# Sheet.net
KiCad netlist of a schematic drawn in Altium Designer
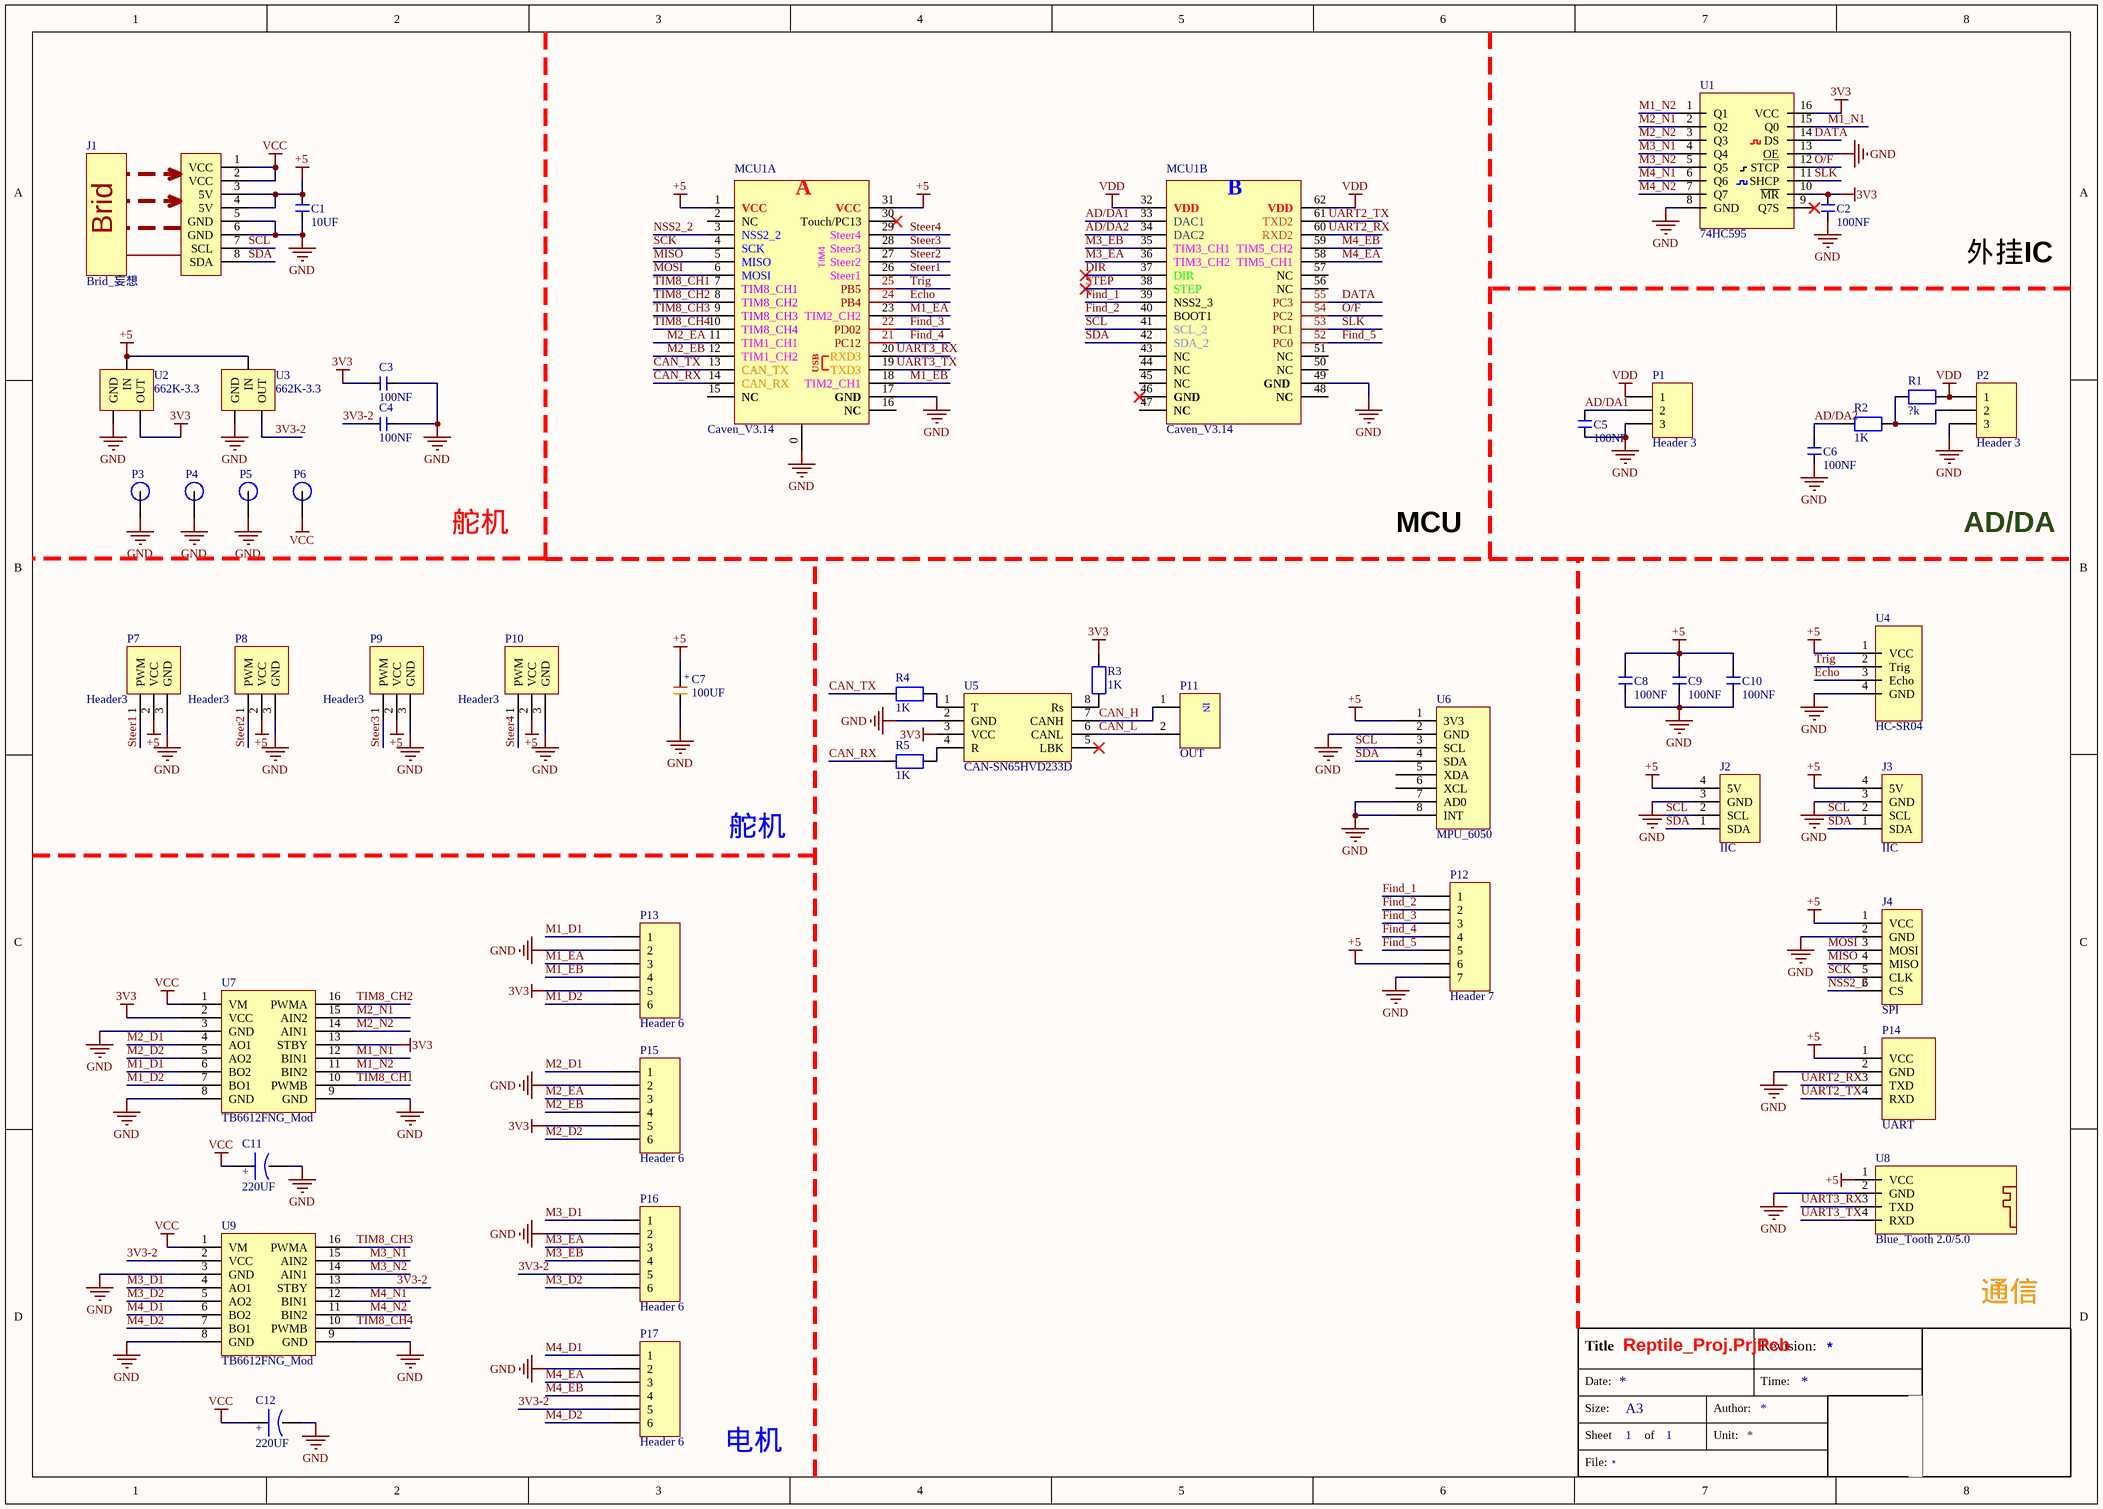
[diagram p0: Sheet.SchDoc]

(export (version "E")
  (design (tool "Eeschema 10.0.6"))
  (components
    (comp (ref "C1")
      (value "10UF")
      (footprint "CAP_1206")
      (description "CAP  12~50V")
      (libsource (lib "User") (part "CAP"))
    )
    (comp (ref "C2")
      (value "100NF")
      (footprint "CAP_0603")
      (description "CAP  12~50V")
      (libsource (lib "User") (part "CAP"))
    )
    (comp (ref "C3")
      (value "100NF")
      (footprint "CAP_0603")
      (description "CAP  12~50V")
      (libsource (lib "User") (part "CAP"))
    )
    (comp (ref "C4")
      (value "100NF")
      (footprint "CAP_0603")
      (description "CAP  12~50V")
      (libsource (lib "User") (part "CAP"))
    )
    (comp (ref "C5")
      (value "100NF")
      (footprint "CAP_0603")
      (description "CAP  12~50V")
      (libsource (lib "User") (part "CAP"))
    )
    (comp (ref "C6")
      (value "100NF")
      (footprint "CAP_0603")
      (description "CAP  12~50V")
      (libsource (lib "User") (part "CAP"))
    )
    (comp (ref "C7")
      (value "100UF")
      (footprint "CAP_3528_B")
      (description "CAP  6~12V  钽电容")
      (libsource (lib "User") (part "CAP_TA"))
    )
    (comp (ref "C8")
      (value "100NF")
      (footprint "CAP_0603")
      (description "CAP  12~50V")
      (libsource (lib "User") (part "CAP"))
    )
    (comp (ref "C9")
      (value "100NF")
      (footprint "CAP_0603")
      (description "CAP  12~50V")
      (libsource (lib "User") (part "CAP"))
    )
    (comp (ref "C10")
      (value "100NF")
      (footprint "CAP_0603")
      (description "CAP  12~50V")
      (libsource (lib "User") (part "CAP"))
    )
    (comp (ref "C11")
      (value "220UF")
      (footprint "CAPE_E")
      (description "CAP 12V ~ 50V   电解电容")
      (libsource (lib "User") (part "CAP_BIG"))
    )
    (comp (ref "C12")
      (value "220UF")
      (footprint "CAPE_E")
      (description "CAP 12V ~ 50V   电解电容")
      (libsource (lib "User") (part "CAP_BIG"))
    )
    (comp (ref "J1")
      (value "Brid_妄想")
      (footprint "Brid")
      (description "Brid")
      (libsource (lib "User") (part "Brid"))
    )
    (comp (ref "J2")
      (value "IIC")
      (footprint "Header 2.54X4")
      (description "Heard")
      (libsource (lib "User") (part "IIC"))
    )
    (comp (ref "J3")
      (value "IIC")
      (footprint "IIC-XH2.54-4PIN")
      (description "Heard")
      (libsource (lib "User") (part "IIC"))
    )
    (comp (ref "J4")
      (value "SPI")
      (footprint "Header 2.54X6")
      (description "Heard")
      (libsource (lib "User") (part "SPI"))
    )
    (comp (ref "MCU1")
      (value "Caven_V3.14")
      (footprint "Caven_3.14")
      (description "MCU_STM32F103RE")
      (libsource (lib "User") (part "Caven_V3.14"))
    )
    (comp (ref "P1")
      (value "Header 3")
      (footprint "Header 2.54X3")
      (description "Header, 3-Pin")
      (fields (field (name "PUBLISHER") "Altium Limited"))
      (libsource (lib "Miscellaneous Connectors") (part "Header 3"))
    )
    (comp (ref "P2")
      (value "Header 3")
      (footprint "Header 2.54X3")
      (description "Header, 3-Pin")
      (fields (field (name "PUBLISHER") "Altium Limited"))
      (libsource (lib "Miscellaneous Connectors") (part "Header 3"))
    )
    (comp (ref "P3")
      (value "铜柱6m")
      (footprint "M3x6_L-Type")
      (description "IN-OUT")
      (libsource (lib "User") (part "Pillar"))
    )
    (comp (ref "P4")
      (value "铜柱6m")
      (footprint "M3x6_L-Type")
      (description "IN-OUT")
      (libsource (lib "User") (part "Pillar"))
    )
    (comp (ref "P5")
      (value "铜柱6m")
      (footprint "M3x6_L-Type")
      (description "IN-OUT")
      (libsource (lib "User") (part "Pillar"))
    )
    (comp (ref "P6")
      (value "铜柱6m")
      (footprint "M3x6_L-Type")
      (description "IN-OUT")
      (libsource (lib "User") (part "Pillar"))
    )
    (comp (ref "P7")
      (value "Header3")
      (footprint "PWM_Steer-F")
      (description "Header")
      (libsource (lib "User") (part "PWM_D"))
    )
    (comp (ref "P8")
      (value "Header3")
      (footprint "PWM_Steer-B")
      (description "Header")
      (libsource (lib "User") (part "PWM_D"))
    )
    (comp (ref "P9")
      (value "Header3")
      (footprint "PWM_Steer-F")
      (description "Header")
      (libsource (lib "User") (part "PWM_D"))
    )
    (comp (ref "P10")
      (value "Header3")
      (footprint "PWM_Steer-B")
      (description "Header")
      (libsource (lib "User") (part "PWM_D"))
    )
    (comp (ref "P11")
      (value "OUT")
      (footprint "PIN-2_5.08")
      (description "Header")
      (libsource (lib "User") (part "IN _2PIN"))
    )
    (comp (ref "P12")
      (value "Header 7")
      (footprint "Header H 2.54X7")
      (description "Header, 7-Pin")
      (fields (field (name "PUBLISHER") "Altium Limited"))
      (libsource (lib "Miscellaneous Connectors") (part "Header 7"))
    )
    (comp (ref "P13")
      (value "Header 6")
      (footprint "XH2.54-WI-6P")
      (description "Header, 6-Pin")
      (fields (field (name "PUBLISHER") "Altium Limited"))
      (libsource (lib "Miscellaneous Connectors") (part "Header 6"))
    )
    (comp (ref "P14")
      (value "UART")
      (footprint "UART")
      (description "Header")
      (libsource (lib "User") (part "UART"))
    )
    (comp (ref "P15")
      (value "Header 6")
      (footprint "XH2.54-WI-6P")
      (description "Header, 6-Pin")
      (fields (field (name "PUBLISHER") "Altium Limited"))
      (libsource (lib "Miscellaneous Connectors") (part "Header 6"))
    )
    (comp (ref "P16")
      (value "Header 6")
      (footprint "XH2.54-WI-6P")
      (description "Header, 6-Pin")
      (fields (field (name "PUBLISHER") "Altium Limited"))
      (libsource (lib "Miscellaneous Connectors") (part "Header 6"))
    )
    (comp (ref "P17")
      (value "Header 6")
      (footprint "XH2.54-WI-6P")
      (description "Header, 6-Pin")
      (fields (field (name "PUBLISHER") "Altium Limited"))
      (libsource (lib "Miscellaneous Connectors") (part "Header 6"))
    )
    (comp (ref "R1")
      (value "?k")
      (footprint "RESC_0603_2")
      (description "RES 贴片")
      (libsource (lib "User") (part "RES"))
    )
    (comp (ref "R2")
      (value "1K")
      (footprint "RESC_0603_2")
      (description "RES 贴片")
      (libsource (lib "User") (part "RES"))
    )
    (comp (ref "R3")
      (value "1K")
      (footprint "RESC_0603_2")
      (description "RES 贴片")
      (libsource (lib "User") (part "RES"))
    )
    (comp (ref "R4")
      (value "1K")
      (footprint "RESC_0603_2")
      (description "RES 贴片")
      (libsource (lib "User") (part "RES"))
    )
    (comp (ref "R5")
      (value "1K")
      (footprint "RESC_0603_2")
      (description "RES 贴片")
      (libsource (lib "User") (part "RES"))
    )
    (comp (ref "U1")
      (value "74HC595")
      (footprint "SOIC_16")
      (description "IC")
      (libsource (lib "User") (part "74HC595"))
    )
    (comp (ref "U2")
      (value "662K-3.3")
      (footprint "SOT23_3")
      (description "DC-DC")
      (libsource (lib "User") (part "662K"))
    )
    (comp (ref "U3")
      (value "662K-3.3")
      (footprint "SOT23_3")
      (description "DC-DC")
      (libsource (lib "User") (part "662K"))
    )
    (comp (ref "U4")
      (value "HC-SR04")
      (footprint "Ultrasonic")
      (description "Mode")
      (libsource (lib "User") (part "Ultrasonic"))
    )
    (comp (ref "U5")
      (value "CAN-SN65HVD233D")
      (footprint "SOIC_8")
      (description "CAN")
      (libsource (lib "User") (part "CAN"))
    )
    (comp (ref "U6")
      (value "MPU_6050")
      (footprint "MPU-G521")
      (description "MODE")
      (libsource (lib "User") (part "MPU_6050"))
    )
    (comp (ref "U7")
      (value "TB6612FNG_Mod")
      (footprint "TB6612FNG")
      (description "MODE")
      (libsource (lib "User") (part "TB6612FNG_Mod"))
    )
    (comp (ref "U8")
      (value "Blue_Tooth 2.0/5.0")
      (footprint "Header F 2.54X4")
      (description "MODE")
      (libsource (lib "User") (part "HC-02/06"))
    )
    (comp (ref "U9")
      (value "TB6612FNG_Mod")
      (footprint "TB6612FNG")
      (description "MODE")
      (libsource (lib "User") (part "TB6612FNG_Mod"))
    )
  )
  (nets
    (net (code "1") (name "+5") (class "Default")
      (node (ref "C1") (pin "1") (pinfunction "0_1") (pintype "passive"))
      (node (ref "C10") (pin "2") (pinfunction "0_2") (pintype "passive"))
      (node (ref "C7") (pin "1") (pinfunction "0_1") (pintype "passive"))
      (node (ref "C8") (pin "2") (pinfunction "0_2") (pintype "passive"))
      (node (ref "C9") (pin "2") (pinfunction "0_2") (pintype "passive"))
      (node (ref "J1") (pin "3") (pinfunction "5V_3") (pintype "passive"))
      (node (ref "J1") (pin "4") (pinfunction "5V_4") (pintype "passive"))
      (node (ref "J2") (pin "4") (pinfunction "5V_4") (pintype "passive"))
      (node (ref "J3") (pin "4") (pinfunction "5V_4") (pintype "passive"))
      (node (ref "J4") (pin "1") (pinfunction "VCC_1") (pintype "passive"))
      (node (ref "MCU1") (pin "1") (pinfunction "VCC_1") (pintype "passive"))
      (node (ref "MCU1") (pin "31") (pinfunction "VCC_31") (pintype "passive"))
      (node (ref "P10") (pin "2") (pinfunction "VCC_2") (pintype "passive"))
      (node (ref "P12") (pin "6") (pinfunction "6_6") (pintype "passive"))
      (node (ref "P14") (pin "1") (pinfunction "VCC_1") (pintype "passive"))
      (node (ref "P7") (pin "2") (pinfunction "VCC_2") (pintype "passive"))
      (node (ref "P8") (pin "2") (pinfunction "VCC_2") (pintype "passive"))
      (node (ref "P9") (pin "2") (pinfunction "VCC_2") (pintype "passive"))
      (node (ref "U2") (pin "3") (pinfunction "IN_3") (pintype "passive"))
      (node (ref "U3") (pin "3") (pinfunction "IN_3") (pintype "passive"))
      (node (ref "U4") (pin "1") (pinfunction "VCC_1") (pintype "passive"))
      (node (ref "U6") (pin "1") (pinfunction "3V3_1") (pintype "passive"))
      (node (ref "U8") (pin "1") (pinfunction "VCC_1") (pintype "passive"))
    )
    (net (code "2") (name "/3V3-2") (class "Default")
      (node (ref "C4") (pin "2") (pinfunction "0_2") (pintype "passive"))
      (node (ref "P16") (pin "5") (pinfunction "5_5") (pintype "passive"))
      (node (ref "P17") (pin "5") (pinfunction "5_5") (pintype "passive"))
      (node (ref "U3") (pin "2") (pinfunction "OUT_2") (pintype "passive"))
      (node (ref "U9") (pin "13") (pinfunction "STBY_13") (pintype "passive"))
      (node (ref "U9") (pin "2") (pinfunction "VCC_2") (pintype "passive"))
    )
    (net (code "3") (name "/AD{slash}DA1") (class "Default")
      (node (ref "C5") (pin "2") (pinfunction "0_2") (pintype "passive"))
      (node (ref "MCU1") (pin "33") (pinfunction "DAC1_33") (pintype "passive"))
      (node (ref "P1") (pin "2") (pinfunction "2_2") (pintype "passive"))
    )
    (net (code "4") (name "/AD{slash}DA2") (class "Default")
      (node (ref "C6") (pin "2") (pinfunction "0_2") (pintype "passive"))
      (node (ref "MCU1") (pin "34") (pinfunction "DAC2_34") (pintype "passive"))
      (node (ref "R2") (pin "2") (pinfunction "2_2") (pintype "passive"))
    )
    (net (code "5") (name "/CAN_H") (class "Default")
      (node (ref "P11") (pin "1") (pintype "passive"))
      (node (ref "U5") (pin "7") (pinfunction "CANH_7") (pintype "passive"))
    )
    (net (code "6") (name "/CAN_L") (class "Default")
      (node (ref "P11") (pin "2") (pintype "passive"))
      (node (ref "U5") (pin "6") (pinfunction "CANL_6") (pintype "passive"))
    )
    (net (code "7") (name "/CAN_RX") (class "Default")
      (node (ref "MCU1") (pin "14") (pinfunction "CAN_RX_14") (pintype "passive"))
      (node (ref "R5") (pin "1") (pinfunction "1_1") (pintype "passive"))
    )
    (net (code "8") (name "/CAN_TX") (class "Default")
      (node (ref "MCU1") (pin "13") (pinfunction "CAN_TX_13") (pintype "passive"))
      (node (ref "R4") (pin "1") (pinfunction "1_1") (pintype "passive"))
    )
    (net (code "9") (name "/DATA") (class "Default")
      (node (ref "MCU1") (pin "55") (pinfunction "PC3_55") (pintype "passive"))
      (node (ref "U1") (pin "14") (pinfunction "DS_14") (pintype "passive"))
    )
    (net (code "10") (name "/DIR") (class "Default")
      (node (ref "MCU1") (pin "37") (pinfunction "DIR_37") (pintype "passive+no_connect"))
    )
    (net (code "11") (name "/Echo") (class "Default")
      (node (ref "MCU1") (pin "24") (pinfunction "PB4_24") (pintype "passive"))
      (node (ref "U4") (pin "3") (pinfunction "Echo_3") (pintype "passive"))
    )
    (net (code "12") (name "/Find_1") (class "Default")
      (node (ref "MCU1") (pin "39") (pinfunction "NSS2_3_39") (pintype "passive"))
      (node (ref "P12") (pin "1") (pinfunction "1_1") (pintype "passive"))
    )
    (net (code "13") (name "/Find_2") (class "Default")
      (node (ref "MCU1") (pin "40") (pinfunction "BOOT1_40") (pintype "passive"))
      (node (ref "P12") (pin "2") (pinfunction "2_2") (pintype "passive"))
    )
    (net (code "14") (name "/Find_3") (class "Default")
      (node (ref "MCU1") (pin "22") (pinfunction "PD02_22") (pintype "passive"))
      (node (ref "P12") (pin "3") (pinfunction "3_3") (pintype "passive"))
    )
    (net (code "15") (name "/Find_4") (class "Default")
      (node (ref "MCU1") (pin "21") (pinfunction "PC12_21") (pintype "passive"))
      (node (ref "P12") (pin "4") (pinfunction "4_4") (pintype "passive"))
    )
    (net (code "16") (name "/Find_5") (class "Default")
      (node (ref "MCU1") (pin "52") (pinfunction "PC0_52") (pintype "passive"))
      (node (ref "P12") (pin "5") (pinfunction "5_5") (pintype "passive"))
    )
    (net (code "17") (name "/M1_D1") (class "Default")
      (node (ref "P13") (pin "1") (pinfunction "1_1") (pintype "passive"))
      (node (ref "U7") (pin "6") (pinfunction "BO2_6") (pintype "passive"))
    )
    (net (code "18") (name "/M1_D2") (class "Default")
      (node (ref "P13") (pin "6") (pinfunction "6_6") (pintype "passive"))
      (node (ref "U7") (pin "7") (pinfunction "BO1_7") (pintype "passive"))
    )
    (net (code "19") (name "/M1_EA") (class "Default")
      (node (ref "MCU1") (pin "23") (pinfunction "TIM2_CH2_23") (pintype "passive"))
      (node (ref "P13") (pin "3") (pinfunction "3_3") (pintype "passive"))
    )
    (net (code "20") (name "/M1_EB") (class "Default")
      (node (ref "MCU1") (pin "18") (pinfunction "TIM2_CH1_18") (pintype "passive"))
      (node (ref "P13") (pin "4") (pinfunction "4_4") (pintype "passive"))
    )
    (net (code "21") (name "/M1_N1") (class "Default")
      (node (ref "U1") (pin "15") (pinfunction "Q0_15") (pintype "passive"))
      (node (ref "U7") (pin "12") (pinfunction "BIN1_12") (pintype "passive"))
    )
    (net (code "22") (name "/M1_N2") (class "Default")
      (node (ref "U1") (pin "1") (pinfunction "Q1_1") (pintype "passive"))
      (node (ref "U7") (pin "11") (pinfunction "BIN2_11") (pintype "passive"))
    )
    (net (code "23") (name "/M2_D1") (class "Default")
      (node (ref "P15") (pin "1") (pinfunction "1_1") (pintype "passive"))
      (node (ref "U7") (pin "4") (pinfunction "AO1_4") (pintype "passive"))
    )
    (net (code "24") (name "/M2_D2") (class "Default")
      (node (ref "P15") (pin "6") (pinfunction "6_6") (pintype "passive"))
      (node (ref "U7") (pin "5") (pinfunction "AO2_5") (pintype "passive"))
    )
    (net (code "25") (name "/M2_EA") (class "Default")
      (node (ref "MCU1") (pin "11") (pinfunction "TIM1_CH1_11") (pintype "passive"))
      (node (ref "P15") (pin "3") (pinfunction "3_3") (pintype "passive"))
    )
    (net (code "26") (name "/M2_EB") (class "Default")
      (node (ref "MCU1") (pin "12") (pinfunction "TIM1_CH2_12") (pintype "passive"))
      (node (ref "P15") (pin "4") (pinfunction "4_4") (pintype "passive"))
    )
    (net (code "27") (name "/M2_N1") (class "Default")
      (node (ref "U1") (pin "2") (pinfunction "Q2_2") (pintype "passive"))
      (node (ref "U7") (pin "15") (pinfunction "AIN2_15") (pintype "passive"))
    )
    (net (code "28") (name "/M2_N2") (class "Default")
      (node (ref "U1") (pin "3") (pinfunction "Q3_3") (pintype "passive"))
      (node (ref "U7") (pin "14") (pinfunction "AIN1_14") (pintype "passive"))
    )
    (net (code "29") (name "/M3_D1") (class "Default")
      (node (ref "P16") (pin "1") (pinfunction "1_1") (pintype "passive"))
      (node (ref "U9") (pin "4") (pinfunction "AO1_4") (pintype "passive"))
    )
    (net (code "30") (name "/M3_D2") (class "Default")
      (node (ref "P16") (pin "6") (pinfunction "6_6") (pintype "passive"))
      (node (ref "U9") (pin "5") (pinfunction "AO2_5") (pintype "passive"))
    )
    (net (code "31") (name "/M3_EA") (class "Default")
      (node (ref "MCU1") (pin "36") (pinfunction "TIM3_CH2_36") (pintype "passive"))
      (node (ref "P16") (pin "3") (pinfunction "3_3") (pintype "passive"))
    )
    (net (code "32") (name "/M3_EB") (class "Default")
      (node (ref "MCU1") (pin "35") (pinfunction "TIM3_CH1_35") (pintype "passive"))
      (node (ref "P16") (pin "4") (pinfunction "4_4") (pintype "passive"))
    )
    (net (code "33") (name "/M3_N1") (class "Default")
      (node (ref "U1") (pin "4") (pinfunction "Q4_4") (pintype "passive"))
      (node (ref "U9") (pin "15") (pinfunction "AIN2_15") (pintype "passive"))
    )
    (net (code "34") (name "/M3_N2") (class "Default")
      (node (ref "U1") (pin "5") (pinfunction "Q5_5") (pintype "passive"))
      (node (ref "U9") (pin "14") (pinfunction "AIN1_14") (pintype "passive"))
    )
    (net (code "35") (name "/M4_D1") (class "Default")
      (node (ref "P17") (pin "1") (pinfunction "1_1") (pintype "passive"))
      (node (ref "U9") (pin "6") (pinfunction "BO2_6") (pintype "passive"))
    )
    (net (code "36") (name "/M4_D2") (class "Default")
      (node (ref "P17") (pin "6") (pinfunction "6_6") (pintype "passive"))
      (node (ref "U9") (pin "7") (pinfunction "BO1_7") (pintype "passive"))
    )
    (net (code "37") (name "/M4_EA") (class "Default")
      (node (ref "MCU1") (pin "58") (pinfunction "TIM5_CH1_58") (pintype "passive"))
      (node (ref "P17") (pin "3") (pinfunction "3_3") (pintype "passive"))
    )
    (net (code "38") (name "/M4_EB") (class "Default")
      (node (ref "MCU1") (pin "59") (pinfunction "TIM5_CH2_59") (pintype "passive"))
      (node (ref "P17") (pin "4") (pinfunction "4_4") (pintype "passive"))
    )
    (net (code "39") (name "/M4_N1") (class "Default")
      (node (ref "U1") (pin "6") (pinfunction "Q6_6") (pintype "passive"))
      (node (ref "U9") (pin "12") (pinfunction "BIN1_12") (pintype "passive"))
    )
    (net (code "40") (name "/M4_N2") (class "Default")
      (node (ref "U1") (pin "7") (pinfunction "Q7_7") (pintype "passive"))
      (node (ref "U9") (pin "11") (pinfunction "BIN2_11") (pintype "passive"))
    )
    (net (code "41") (name "/MISO") (class "Default")
      (node (ref "J4") (pin "4") (pinfunction "MISO_4") (pintype "passive"))
      (node (ref "MCU1") (pin "5") (pinfunction "MISO_5") (pintype "passive"))
    )
    (net (code "42") (name "/MOSI") (class "Default")
      (node (ref "J4") (pin "3") (pinfunction "MOSI_3") (pintype "passive"))
      (node (ref "MCU1") (pin "6") (pinfunction "MOSI_6") (pintype "passive"))
    )
    (net (code "43") (name "/NSS2_2") (class "Default")
      (node (ref "J4") (pin "6") (pinfunction "CS_6") (pintype "passive"))
      (node (ref "MCU1") (pin "3") (pinfunction "NSS2_2_3") (pintype "passive"))
    )
    (net (code "44") (name "/O{slash}F") (class "Default")
      (node (ref "MCU1") (pin "54") (pinfunction "PC2_54") (pintype "passive"))
      (node (ref "U1") (pin "12") (pinfunction "STCP_12") (pintype "passive"))
    )
    (net (code "45") (name "/SCK") (class "Default")
      (node (ref "J4") (pin "5") (pinfunction "CLK_5") (pintype "passive"))
      (node (ref "MCU1") (pin "4") (pinfunction "SCK_4") (pintype "passive"))
    )
    (net (code "46") (name "/SCL") (class "Default")
      (node (ref "J1") (pin "7") (pinfunction "SCL_7") (pintype "passive"))
      (node (ref "J2") (pin "2") (pinfunction "SCL_2") (pintype "passive"))
      (node (ref "J3") (pin "2") (pinfunction "SCL_2") (pintype "passive"))
      (node (ref "MCU1") (pin "41") (pinfunction "SCL_2_41") (pintype "passive"))
      (node (ref "U6") (pin "3") (pinfunction "SCL_3") (pintype "passive"))
    )
    (net (code "47") (name "/SDA") (class "Default")
      (node (ref "J1") (pin "8") (pinfunction "SDA_8") (pintype "passive"))
      (node (ref "J2") (pin "1") (pinfunction "SDA_1") (pintype "passive"))
      (node (ref "J3") (pin "1") (pinfunction "SDA_1") (pintype "passive"))
      (node (ref "MCU1") (pin "42") (pinfunction "SDA_2_42") (pintype "passive"))
      (node (ref "U6") (pin "4") (pinfunction "SDA_4") (pintype "passive"))
    )
    (net (code "48") (name "/SLK") (class "Default")
      (node (ref "MCU1") (pin "53") (pinfunction "PC1_53") (pintype "passive"))
      (node (ref "U1") (pin "11") (pinfunction "SHCP_11") (pintype "passive"))
    )
    (net (code "49") (name "/STEP") (class "Default")
      (node (ref "MCU1") (pin "38") (pinfunction "STEP_38") (pintype "passive+no_connect"))
    )
    (net (code "50") (name "/Steer1") (class "Default")
      (node (ref "MCU1") (pin "26") (pinfunction "Steer1_26") (pintype "passive"))
      (node (ref "P7") (pin "1") (pinfunction "PWM_1") (pintype "passive"))
    )
    (net (code "51") (name "/Steer2") (class "Default")
      (node (ref "MCU1") (pin "27") (pinfunction "Steer2_27") (pintype "passive"))
      (node (ref "P8") (pin "1") (pinfunction "PWM_1") (pintype "passive"))
    )
    (net (code "52") (name "/Steer3") (class "Default")
      (node (ref "MCU1") (pin "28") (pinfunction "Steer3_28") (pintype "passive"))
      (node (ref "P9") (pin "1") (pinfunction "PWM_1") (pintype "passive"))
    )
    (net (code "53") (name "/Steer4") (class "Default")
      (node (ref "MCU1") (pin "29") (pinfunction "Steer4_29") (pintype "passive"))
      (node (ref "P10") (pin "1") (pinfunction "PWM_1") (pintype "passive"))
    )
    (net (code "54") (name "/TIM8_CH1") (class "Default")
      (node (ref "MCU1") (pin "7") (pinfunction "TIM8_CH1_7") (pintype "passive"))
      (node (ref "U7") (pin "10") (pinfunction "PWMB_10") (pintype "passive"))
    )
    (net (code "55") (name "/TIM8_CH2") (class "Default")
      (node (ref "MCU1") (pin "8") (pinfunction "TIM8_CH2_8") (pintype "passive"))
      (node (ref "U7") (pin "16") (pinfunction "PWMA_16") (pintype "passive"))
    )
    (net (code "56") (name "/TIM8_CH3") (class "Default")
      (node (ref "MCU1") (pin "9") (pinfunction "TIM8_CH3_9") (pintype "passive"))
      (node (ref "U9") (pin "16") (pinfunction "PWMA_16") (pintype "passive"))
    )
    (net (code "57") (name "/TIM8_CH4") (class "Default")
      (node (ref "MCU1") (pin "10") (pinfunction "TIM8_CH4_10") (pintype "passive"))
      (node (ref "U9") (pin "10") (pinfunction "PWMB_10") (pintype "passive"))
    )
    (net (code "58") (name "/Trig") (class "Default")
      (node (ref "MCU1") (pin "25") (pinfunction "PB5_25") (pintype "passive"))
      (node (ref "U4") (pin "2") (pinfunction "Trig_2") (pintype "passive"))
    )
    (net (code "59") (name "/UART2_RX") (class "Default")
      (node (ref "MCU1") (pin "60") (pinfunction "RXD2_60") (pintype "passive"))
      (node (ref "P14") (pin "3") (pinfunction "TXD_3") (pintype "passive"))
    )
    (net (code "60") (name "/UART2_TX") (class "Default")
      (node (ref "MCU1") (pin "61") (pinfunction "TXD2_61") (pintype "passive"))
      (node (ref "P14") (pin "4") (pinfunction "RXD_4") (pintype "passive"))
    )
    (net (code "61") (name "/UART3_RX") (class "Default")
      (node (ref "MCU1") (pin "20") (pinfunction "RXD3_20") (pintype "passive"))
      (node (ref "U8") (pin "3") (pinfunction "TXD_3") (pintype "passive"))
    )
    (net (code "62") (name "/UART3_TX") (class "Default")
      (node (ref "MCU1") (pin "19") (pinfunction "TXD3_19") (pintype "passive"))
      (node (ref "U8") (pin "4") (pinfunction "RXD_4") (pintype "passive"))
    )
    (net (code "63") (name "3V3") (class "Default")
      (node (ref "C2") (pin "2") (pinfunction "0_2") (pintype "passive"))
      (node (ref "C3") (pin "2") (pinfunction "0_2") (pintype "passive"))
      (node (ref "P13") (pin "5") (pinfunction "5_5") (pintype "passive"))
      (node (ref "P15") (pin "5") (pinfunction "5_5") (pintype "passive"))
      (node (ref "R3") (pin "2") (pinfunction "2_2") (pintype "passive"))
      (node (ref "U1") (pin "10") (pinfunction "~{MR}_10") (pintype "passive"))
      (node (ref "U1") (pin "16") (pinfunction "VCC_16") (pintype "passive"))
      (node (ref "U2") (pin "2") (pinfunction "OUT_2") (pintype "passive"))
      (node (ref "U5") (pin "3") (pinfunction "VCC_3") (pintype "passive"))
      (node (ref "U7") (pin "13") (pinfunction "STBY_13") (pintype "passive"))
      (node (ref "U7") (pin "2") (pinfunction "VCC_2") (pintype "passive"))
    )
    (net (code "64") (name "GND") (class "Default")
      (node (ref "C1") (pin "2") (pinfunction "0_2") (pintype "passive"))
      (node (ref "C10") (pin "1") (pinfunction "0_1") (pintype "passive"))
      (node (ref "C11") (pin "2") (pinfunction "0_2") (pintype "passive"))
      (node (ref "C12") (pin "2") (pinfunction "0_2") (pintype "passive"))
      (node (ref "C2") (pin "1") (pinfunction "0_1") (pintype "passive"))
      (node (ref "C3") (pin "1") (pinfunction "0_1") (pintype "passive"))
      (node (ref "C4") (pin "1") (pinfunction "0_1") (pintype "passive"))
      (node (ref "C5") (pin "1") (pinfunction "0_1") (pintype "passive"))
      (node (ref "C6") (pin "1") (pinfunction "0_1") (pintype "passive"))
      (node (ref "C7") (pin "2") (pinfunction "0_2") (pintype "passive"))
      (node (ref "C8") (pin "1") (pinfunction "0_1") (pintype "passive"))
      (node (ref "C9") (pin "1") (pinfunction "0_1") (pintype "passive"))
      (node (ref "J1") (pin "5") (pinfunction "GND_5") (pintype "passive"))
      (node (ref "J1") (pin "6") (pinfunction "GND_6") (pintype "passive"))
      (node (ref "J2") (pin "3") (pinfunction "GND_3") (pintype "passive"))
      (node (ref "J3") (pin "3") (pinfunction "GND_3") (pintype "passive"))
      (node (ref "J4") (pin "2") (pinfunction "GND_2") (pintype "passive"))
      (node (ref "MCU1") (pin "0") (pinfunction "0_0") (pintype "passive"))
      (node (ref "MCU1") (pin "17") (pinfunction "GND_17") (pintype "passive"))
      (node (ref "MCU1") (pin "49") (pinfunction "GND_49") (pintype "passive"))
      (node (ref "P1") (pin "3") (pinfunction "3_3") (pintype "passive"))
      (node (ref "P10") (pin "3") (pinfunction "GND_3") (pintype "passive"))
      (node (ref "P12") (pin "7") (pinfunction "7_7") (pintype "passive"))
      (node (ref "P13") (pin "2") (pinfunction "2_2") (pintype "passive"))
      (node (ref "P14") (pin "2") (pinfunction "GND_2") (pintype "passive"))
      (node (ref "P15") (pin "2") (pinfunction "2_2") (pintype "passive"))
      (node (ref "P16") (pin "2") (pinfunction "2_2") (pintype "passive"))
      (node (ref "P17") (pin "2") (pinfunction "2_2") (pintype "passive"))
      (node (ref "P2") (pin "3") (pinfunction "3_3") (pintype "passive"))
      (node (ref "P3") (pin "1") (pinfunction "IO_1") (pintype "passive"))
      (node (ref "P4") (pin "1") (pinfunction "IO_1") (pintype "passive"))
      (node (ref "P5") (pin "1") (pinfunction "IO_1") (pintype "passive"))
      (node (ref "P7") (pin "3") (pinfunction "GND_3") (pintype "passive"))
      (node (ref "P8") (pin "3") (pinfunction "GND_3") (pintype "passive"))
      (node (ref "P9") (pin "3") (pinfunction "GND_3") (pintype "passive"))
      (node (ref "U1") (pin "13") (pinfunction "OE_13") (pintype "passive"))
      (node (ref "U1") (pin "8") (pinfunction "GND_8") (pintype "passive"))
      (node (ref "U2") (pin "1") (pinfunction "GND_1") (pintype "passive"))
      (node (ref "U3") (pin "1") (pinfunction "GND_1") (pintype "passive"))
      (node (ref "U4") (pin "4") (pinfunction "GND_4") (pintype "passive"))
      (node (ref "U5") (pin "2") (pinfunction "GND_2") (pintype "passive"))
      (node (ref "U6") (pin "2") (pinfunction "GND_2") (pintype "passive"))
      (node (ref "U6") (pin "7") (pinfunction "AD0_7") (pintype "passive"))
      (node (ref "U6") (pin "8") (pinfunction "INT_8") (pintype "passive"))
      (node (ref "U7") (pin "3") (pinfunction "GND_3") (pintype "passive"))
      (node (ref "U7") (pin "8") (pinfunction "GND_8") (pintype "passive"))
      (node (ref "U7") (pin "9") (pinfunction "GND_9") (pintype "passive"))
      (node (ref "U8") (pin "2") (pinfunction "GND_2") (pintype "passive"))
      (node (ref "U9") (pin "3") (pinfunction "GND_3") (pintype "passive"))
      (node (ref "U9") (pin "8") (pinfunction "GND_8") (pintype "passive"))
      (node (ref "U9") (pin "9") (pinfunction "GND_9") (pintype "passive"))
    )
    (net (code "65") (name "Net-(P2-Pad2)") (class "Default")
      (node (ref "P2") (pin "2") (pinfunction "2_2") (pintype "passive"))
      (node (ref "R1") (pin "1") (pinfunction "1_1") (pintype "passive"))
      (node (ref "R2") (pin "1") (pinfunction "1_1") (pintype "passive"))
    )
    (net (code "66") (name "Net-(U5-R)") (class "Default")
      (node (ref "R5") (pin "2") (pinfunction "2_2") (pintype "passive"))
      (node (ref "U5") (pin "4") (pinfunction "R_4") (pintype "passive"))
    )
    (net (code "67") (name "Net-(U5-Rs)") (class "Default")
      (node (ref "R3") (pin "1") (pinfunction "1_1") (pintype "passive"))
      (node (ref "U5") (pin "8") (pinfunction "Rs_8") (pintype "passive"))
    )
    (net (code "68") (name "Net-(U5-T)") (class "Default")
      (node (ref "R4") (pin "2") (pinfunction "2_2") (pintype "passive"))
      (node (ref "U5") (pin "1") (pinfunction "T_1") (pintype "passive"))
    )
    (net (code "69") (name "VCC") (class "Default")
      (node (ref "C11") (pin "1") (pinfunction "0_1") (pintype "passive"))
      (node (ref "C12") (pin "1") (pinfunction "0_1") (pintype "passive"))
      (node (ref "J1") (pin "1") (pinfunction "VCC_1") (pintype "passive"))
      (node (ref "J1") (pin "2") (pinfunction "VCC_2") (pintype "passive"))
      (node (ref "P6") (pin "1") (pinfunction "IO_1") (pintype "passive"))
      (node (ref "U7") (pin "1") (pinfunction "VM_1") (pintype "passive"))
      (node (ref "U9") (pin "1") (pinfunction "VM_1") (pintype "passive"))
    )
    (net (code "70") (name "VDD") (class "Default")
      (node (ref "MCU1") (pin "32") (pinfunction "VDD_32") (pintype "passive"))
      (node (ref "MCU1") (pin "62") (pinfunction "VDD_62") (pintype "passive"))
      (node (ref "P1") (pin "1") (pinfunction "1_1") (pintype "passive"))
      (node (ref "P2") (pin "1") (pinfunction "1_1") (pintype "passive"))
      (node (ref "R1") (pin "2") (pinfunction "2_2") (pintype "passive"))
    )
    (net (code "71") (name "unconnected-(MCU1A-NC-Pad2)") (class "Default")
      (node (ref "MCU1") (pin "2") (pinfunction "NC_2") (pintype "passive"))
    )
    (net (code "72") (name "unconnected-(MCU1A-NC-Pad15)") (class "Default")
      (node (ref "MCU1") (pin "15") (pinfunction "NC_15") (pintype "passive"))
    )
    (net (code "73") (name "unconnected-(MCU1A-NC-Pad16)") (class "Default")
      (node (ref "MCU1") (pin "16") (pinfunction "NC_16") (pintype "passive"))
    )
    (net (code "74") (name "unconnected-(MCU1A-Touch{slash}PC13-Pad30)") (class "Default")
      (node (ref "MCU1") (pin "30") (pinfunction "Touch/PC13_30") (pintype "passive+no_connect"))
    )
    (net (code "75") (name "unconnected-(MCU1B-GND-Pad46)") (class "Default")
      (node (ref "MCU1") (pin "46") (pinfunction "GND_46") (pintype "passive+no_connect"))
    )
    (net (code "76") (name "unconnected-(MCU1B-NC-Pad43)") (class "Default")
      (node (ref "MCU1") (pin "43") (pinfunction "NC_43") (pintype "passive"))
    )
    (net (code "77") (name "unconnected-(MCU1B-NC-Pad44)") (class "Default")
      (node (ref "MCU1") (pin "44") (pinfunction "NC_44") (pintype "passive"))
    )
    (net (code "78") (name "unconnected-(MCU1B-NC-Pad45)") (class "Default")
      (node (ref "MCU1") (pin "45") (pinfunction "NC_45") (pintype "passive"))
    )
    (net (code "79") (name "unconnected-(MCU1B-NC-Pad47)") (class "Default")
      (node (ref "MCU1") (pin "47") (pinfunction "NC_47") (pintype "passive"))
    )
    (net (code "80") (name "unconnected-(MCU1B-NC-Pad48)") (class "Default")
      (node (ref "MCU1") (pin "48") (pinfunction "NC_48") (pintype "passive"))
    )
    (net (code "81") (name "unconnected-(MCU1B-NC-Pad50)") (class "Default")
      (node (ref "MCU1") (pin "50") (pinfunction "NC_50") (pintype "passive"))
    )
    (net (code "82") (name "unconnected-(MCU1B-NC-Pad51)") (class "Default")
      (node (ref "MCU1") (pin "51") (pinfunction "NC_51") (pintype "passive"))
    )
    (net (code "83") (name "unconnected-(MCU1B-NC-Pad56)") (class "Default")
      (node (ref "MCU1") (pin "56") (pinfunction "NC_56") (pintype "passive"))
    )
    (net (code "84") (name "unconnected-(MCU1B-NC-Pad57)") (class "Default")
      (node (ref "MCU1") (pin "57") (pinfunction "NC_57") (pintype "passive"))
    )
    (net (code "85") (name "unconnected-(U1-Q7S-Pad9)") (class "Default")
      (node (ref "U1") (pin "9") (pinfunction "Q7S_9") (pintype "passive+no_connect"))
    )
    (net (code "86") (name "unconnected-(U5-LBK-Pad5)") (class "Default")
      (node (ref "U5") (pin "5") (pinfunction "LBK_5") (pintype "passive+no_connect"))
    )
    (net (code "87") (name "unconnected-(U6-XCL-Pad6)") (class "Default")
      (node (ref "U6") (pin "6") (pinfunction "XCL_6") (pintype "passive"))
    )
    (net (code "88") (name "unconnected-(U6-XDA-Pad5)") (class "Default")
      (node (ref "U6") (pin "5") (pinfunction "XDA_5") (pintype "passive"))
    )
  )
)
